# extensometro.net
KiCad netlist of a schematic drawn in EAGLE
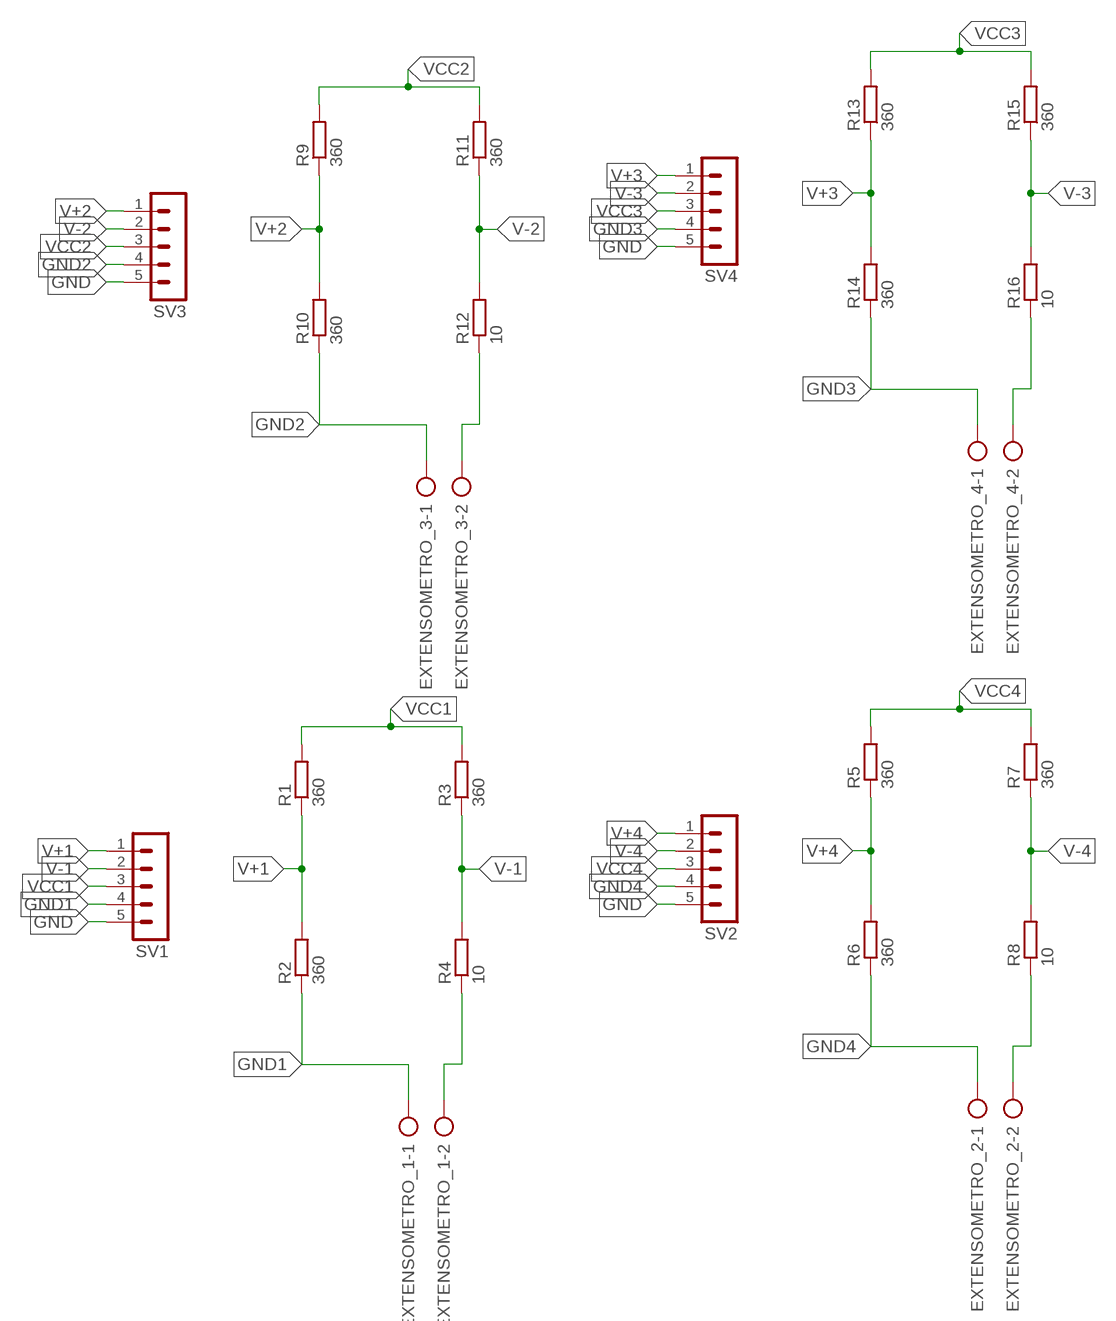
[diagram p0: schematic, sheet 1]

(export (version "E")
  (design (tool "Eeschema 10.0.6"))
  (components
    (comp (ref "EXTENSOMETRO_1")
      (value "AK500/2")
      (footprint "eagle-import:AK500_2")
      (libsource (lib "eagle-import") (part "AK500/2"))
    )
    (comp (ref "EXTENSOMETRO_2")
      (value "AK500/2")
      (footprint "eagle-import:AK500_2")
      (libsource (lib "eagle-import") (part "AK500/2"))
    )
    (comp (ref "EXTENSOMETRO_3")
      (value "AK500/2")
      (footprint "eagle-import:AK500_2")
      (libsource (lib "eagle-import") (part "AK500/2"))
    )
    (comp (ref "EXTENSOMETRO_4")
      (value "AK500/2")
      (footprint "eagle-import:AK500_2")
      (libsource (lib "eagle-import") (part "AK500/2"))
    )
    (comp (ref "R1")
      (value "360")
      (footprint "eagle-import:0207_7")
      (libsource (lib "eagle-import") (part "R-EU_0207/7"))
    )
    (comp (ref "R2")
      (value "360")
      (footprint "eagle-import:0207_7")
      (libsource (lib "eagle-import") (part "R-EU_0207/7"))
    )
    (comp (ref "R3")
      (value "360")
      (footprint "eagle-import:0207_7")
      (libsource (lib "eagle-import") (part "R-EU_0207/7"))
    )
    (comp (ref "R4")
      (value "10")
      (footprint "eagle-import:0207_7")
      (libsource (lib "eagle-import") (part "R-EU_0207/7"))
    )
    (comp (ref "R5")
      (value "360")
      (footprint "eagle-import:0207_7")
      (libsource (lib "eagle-import") (part "R-EU_0207/7"))
    )
    (comp (ref "R6")
      (value "360")
      (footprint "eagle-import:0207_7")
      (libsource (lib "eagle-import") (part "R-EU_0207/7"))
    )
    (comp (ref "R7")
      (value "360")
      (footprint "eagle-import:0207_7")
      (libsource (lib "eagle-import") (part "R-EU_0207/7"))
    )
    (comp (ref "R8")
      (value "10")
      (footprint "eagle-import:0207_7")
      (libsource (lib "eagle-import") (part "R-EU_0207/7"))
    )
    (comp (ref "R9")
      (value "360")
      (footprint "eagle-import:0207_7")
      (libsource (lib "eagle-import") (part "R-EU_0207/7"))
    )
    (comp (ref "R10")
      (value "360")
      (footprint "eagle-import:0207_7")
      (libsource (lib "eagle-import") (part "R-EU_0207/7"))
    )
    (comp (ref "R11")
      (value "360")
      (footprint "eagle-import:0207_7")
      (libsource (lib "eagle-import") (part "R-EU_0207/7"))
    )
    (comp (ref "R12")
      (value "10")
      (footprint "eagle-import:0207_7")
      (libsource (lib "eagle-import") (part "R-EU_0207/7"))
    )
    (comp (ref "R13")
      (value "360")
      (footprint "eagle-import:0207_7")
      (libsource (lib "eagle-import") (part "R-EU_0207/7"))
    )
    (comp (ref "R14")
      (value "360")
      (footprint "eagle-import:0207_7")
      (libsource (lib "eagle-import") (part "R-EU_0207/7"))
    )
    (comp (ref "R15")
      (value "360")
      (footprint "eagle-import:0207_7")
      (libsource (lib "eagle-import") (part "R-EU_0207/7"))
    )
    (comp (ref "R16")
      (value "10")
      (footprint "eagle-import:0207_7")
      (libsource (lib "eagle-import") (part "R-EU_0207/7"))
    )
    (comp (ref "SV1")
      (value "MA05-1")
      (footprint "eagle-import:MA05-1")
      (libsource (lib "eagle-import") (part "MA05-1"))
    )
    (comp (ref "SV2")
      (value "MA05-1")
      (footprint "eagle-import:MA05-1")
      (libsource (lib "eagle-import") (part "MA05-1"))
    )
    (comp (ref "SV3")
      (value "MA05-1")
      (footprint "eagle-import:MA05-1")
      (libsource (lib "eagle-import") (part "MA05-1"))
    )
    (comp (ref "SV4")
      (value "MA05-1")
      (footprint "eagle-import:MA05-1")
      (libsource (lib "eagle-import") (part "MA05-1"))
    )
  )
  (nets
    (net (code "1") (name "GND") (class "Default")
      (node (ref "SV1") (pin "5") (pinfunction "5_5") (pintype "passive"))
      (node (ref "SV2") (pin "5") (pinfunction "5_5") (pintype "passive"))
      (node (ref "SV3") (pin "5") (pinfunction "5_5") (pintype "passive"))
      (node (ref "SV4") (pin "5") (pinfunction "5_5") (pintype "passive"))
    )
    (net (code "2") (name "GND1") (class "Default")
      (node (ref "EXTENSOMETRO_1") (pin "1") (pinfunction "KL_1") (pintype "passive"))
      (node (ref "R2") (pin "1") (pinfunction "1_1") (pintype "passive"))
      (node (ref "SV1") (pin "4") (pinfunction "4_4") (pintype "passive"))
    )
    (net (code "3") (name "GND2") (class "Default")
      (node (ref "EXTENSOMETRO_3") (pin "1") (pinfunction "KL_1") (pintype "passive"))
      (node (ref "R10") (pin "1") (pinfunction "1_1") (pintype "passive"))
      (node (ref "SV3") (pin "4") (pinfunction "4_4") (pintype "passive"))
    )
    (net (code "4") (name "GND3") (class "Default")
      (node (ref "EXTENSOMETRO_4") (pin "1") (pinfunction "KL_1") (pintype "passive"))
      (node (ref "R14") (pin "1") (pinfunction "1_1") (pintype "passive"))
      (node (ref "SV4") (pin "4") (pinfunction "4_4") (pintype "passive"))
    )
    (net (code "5") (name "GND4") (class "Default")
      (node (ref "EXTENSOMETRO_2") (pin "1") (pinfunction "KL_1") (pintype "passive"))
      (node (ref "R6") (pin "1") (pinfunction "1_1") (pintype "passive"))
      (node (ref "SV2") (pin "4") (pinfunction "4_4") (pintype "passive"))
    )
    (net (code "6") (name "Net-(EXTENSOMETRO_1B-KL)") (class "Default")
      (node (ref "EXTENSOMETRO_1") (pin "2") (pinfunction "KL_2") (pintype "passive"))
      (node (ref "R4") (pin "1") (pinfunction "1_1") (pintype "passive"))
    )
    (net (code "7") (name "Net-(EXTENSOMETRO_2B-KL)") (class "Default")
      (node (ref "EXTENSOMETRO_2") (pin "2") (pinfunction "KL_2") (pintype "passive"))
      (node (ref "R8") (pin "1") (pinfunction "1_1") (pintype "passive"))
    )
    (net (code "8") (name "Net-(EXTENSOMETRO_3B-KL)") (class "Default")
      (node (ref "EXTENSOMETRO_3") (pin "2") (pinfunction "KL_2") (pintype "passive"))
      (node (ref "R12") (pin "1") (pinfunction "1_1") (pintype "passive"))
    )
    (net (code "9") (name "Net-(EXTENSOMETRO_4B-KL)") (class "Default")
      (node (ref "EXTENSOMETRO_4") (pin "2") (pinfunction "KL_2") (pintype "passive"))
      (node (ref "R16") (pin "1") (pinfunction "1_1") (pintype "passive"))
    )
    (net (code "10") (name "V+1") (class "Default")
      (node (ref "R1") (pin "1") (pinfunction "1_1") (pintype "passive"))
      (node (ref "R2") (pin "2") (pinfunction "2_2") (pintype "passive"))
      (node (ref "SV1") (pin "1") (pinfunction "1_1") (pintype "passive"))
    )
    (net (code "11") (name "V+2") (class "Default")
      (node (ref "R10") (pin "2") (pinfunction "2_2") (pintype "passive"))
      (node (ref "R9") (pin "1") (pinfunction "1_1") (pintype "passive"))
      (node (ref "SV3") (pin "1") (pinfunction "1_1") (pintype "passive"))
    )
    (net (code "12") (name "V+3") (class "Default")
      (node (ref "R13") (pin "1") (pinfunction "1_1") (pintype "passive"))
      (node (ref "R14") (pin "2") (pinfunction "2_2") (pintype "passive"))
      (node (ref "SV4") (pin "1") (pinfunction "1_1") (pintype "passive"))
    )
    (net (code "13") (name "V+4") (class "Default")
      (node (ref "R5") (pin "1") (pinfunction "1_1") (pintype "passive"))
      (node (ref "R6") (pin "2") (pinfunction "2_2") (pintype "passive"))
      (node (ref "SV2") (pin "1") (pinfunction "1_1") (pintype "passive"))
    )
    (net (code "14") (name "V-1") (class "Default")
      (node (ref "R3") (pin "1") (pinfunction "1_1") (pintype "passive"))
      (node (ref "R4") (pin "2") (pinfunction "2_2") (pintype "passive"))
      (node (ref "SV1") (pin "2") (pinfunction "2_2") (pintype "passive"))
    )
    (net (code "15") (name "V-2") (class "Default")
      (node (ref "R11") (pin "1") (pinfunction "1_1") (pintype "passive"))
      (node (ref "R12") (pin "2") (pinfunction "2_2") (pintype "passive"))
      (node (ref "SV3") (pin "2") (pinfunction "2_2") (pintype "passive"))
    )
    (net (code "16") (name "V-3") (class "Default")
      (node (ref "R15") (pin "1") (pinfunction "1_1") (pintype "passive"))
      (node (ref "R16") (pin "2") (pinfunction "2_2") (pintype "passive"))
      (node (ref "SV4") (pin "2") (pinfunction "2_2") (pintype "passive"))
    )
    (net (code "17") (name "V-4") (class "Default")
      (node (ref "R7") (pin "1") (pinfunction "1_1") (pintype "passive"))
      (node (ref "R8") (pin "2") (pinfunction "2_2") (pintype "passive"))
      (node (ref "SV2") (pin "2") (pinfunction "2_2") (pintype "passive"))
    )
    (net (code "18") (name "VCC1") (class "Default")
      (node (ref "R1") (pin "2") (pinfunction "2_2") (pintype "passive"))
      (node (ref "R3") (pin "2") (pinfunction "2_2") (pintype "passive"))
      (node (ref "SV1") (pin "3") (pinfunction "3_3") (pintype "passive"))
    )
    (net (code "19") (name "VCC2") (class "Default")
      (node (ref "R11") (pin "2") (pinfunction "2_2") (pintype "passive"))
      (node (ref "R9") (pin "2") (pinfunction "2_2") (pintype "passive"))
      (node (ref "SV3") (pin "3") (pinfunction "3_3") (pintype "passive"))
    )
    (net (code "20") (name "VCC3") (class "Default")
      (node (ref "R13") (pin "2") (pinfunction "2_2") (pintype "passive"))
      (node (ref "R15") (pin "2") (pinfunction "2_2") (pintype "passive"))
      (node (ref "SV4") (pin "3") (pinfunction "3_3") (pintype "passive"))
    )
    (net (code "21") (name "VCC4") (class "Default")
      (node (ref "R5") (pin "2") (pinfunction "2_2") (pintype "passive"))
      (node (ref "R7") (pin "2") (pinfunction "2_2") (pintype "passive"))
      (node (ref "SV2") (pin "3") (pinfunction "3_3") (pintype "passive"))
    )
  )
)
